# motor7.net
KiCad netlist of a schematic drawn in EAGLE
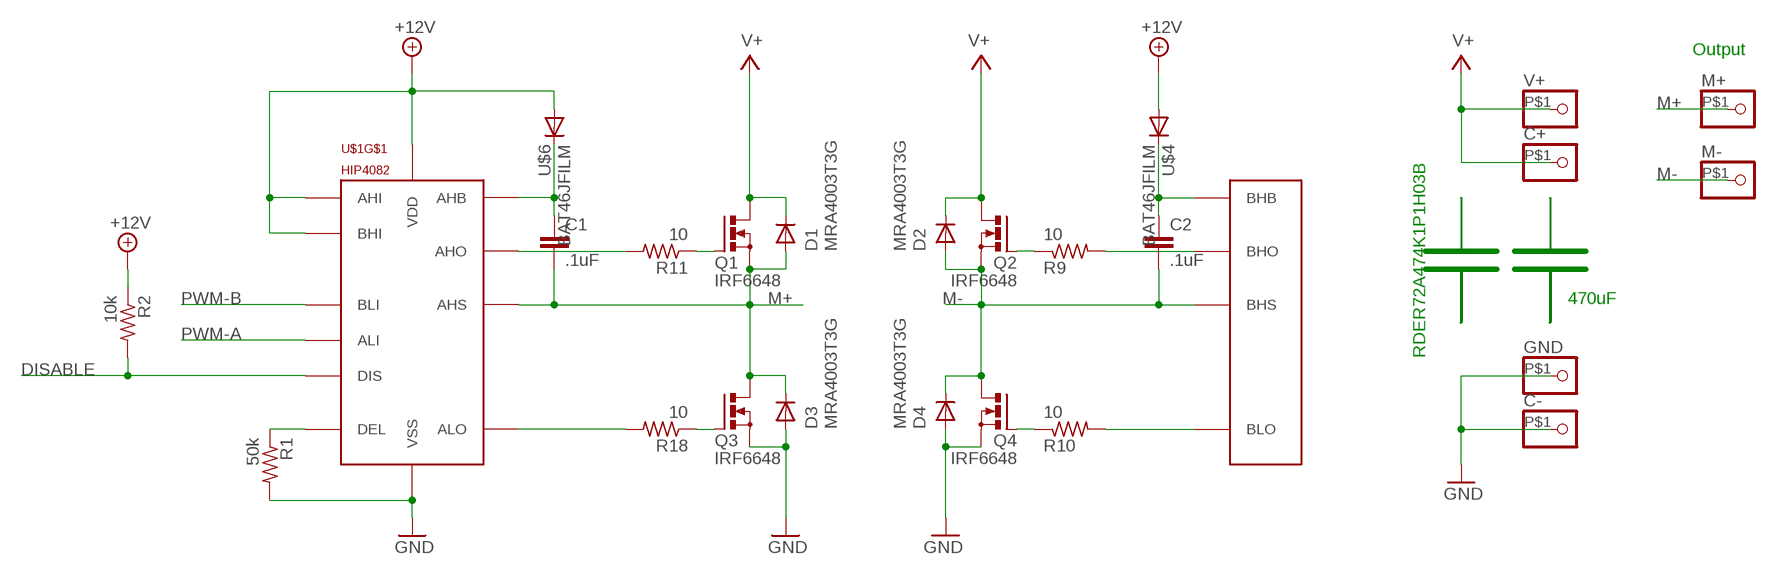
[diagram p0: schematic, sheet 1]
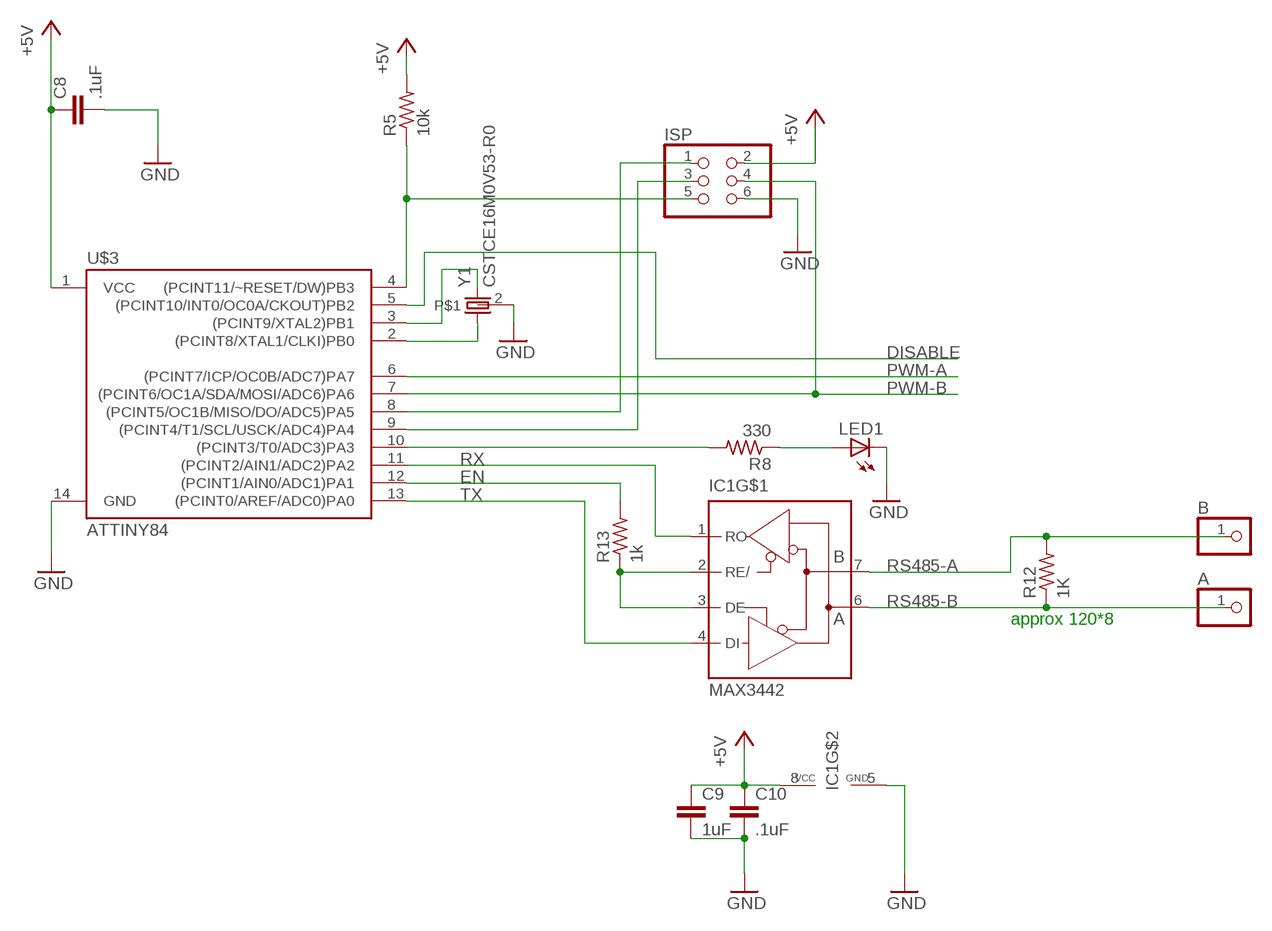
[diagram p1: schematic, sheet 2]
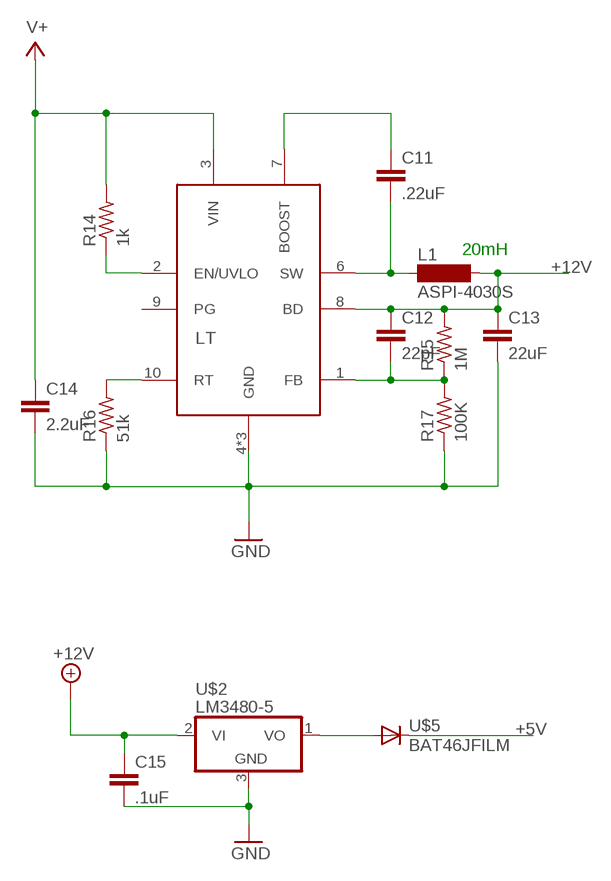
[diagram p2: schematic, sheet 3]

(export (version "E")
  (design (tool "Eeschema 10.0.6"))
  (components
    (comp (ref "A")
      (value "PINHD-1X1")
      (footprint "eagle-import:1X01")
      (libsource (lib "eagle-import") (part "pinhead_PINHD-1X1"))
    )
    (comp (ref "B")
      (value "PINHD-1X1")
      (footprint "eagle-import:1X01")
      (libsource (lib "eagle-import") (part "pinhead_PINHD-1X1"))
    )
    (comp (ref "C8")
      (value ".1uF")
      (footprint "eagle-import:C0603")
      (libsource (lib "eagle-import") (part "C-EUC0603"))
    )
    (comp (ref "C9")
      (value "1uF")
      (footprint "eagle-import:C0603")
      (libsource (lib "eagle-import") (part "C-EUC0603"))
    )
    (comp (ref "C10")
      (value ".1uF")
      (footprint "eagle-import:C0603")
      (libsource (lib "eagle-import") (part "C-EUC0603"))
    )
    (comp (ref "IC1")
      (value "MAX3442")
      (footprint "eagle-import:SO08")
      (fields (field (name "MF") "MAXIM") (field (name "MPN") "MAX481CSA"))
      (libsource (lib "eagle-import") (part "MAX3442"))
    )
    (comp (ref "ISP")
      (value "PINHD-2X3")
      (footprint "eagle-import:2X03")
      (libsource (lib "eagle-import") (part "PINHD-2X3"))
    )
    (comp (ref "LED1")
      (value "LEDCHIPLED_0603")
      (footprint "eagle-import:CHIPLED_0603")
      (libsource (lib "eagle-import") (part "LEDCHIPLED_0603"))
    )
    (comp (ref "R5")
      (value "10k")
      (footprint "eagle-import:R0603")
      (libsource (lib "eagle-import") (part "R-US_R0603"))
    )
    (comp (ref "R8")
      (value "330")
      (footprint "eagle-import:R0603")
      (libsource (lib "eagle-import") (part "R-US_R0603"))
    )
    (comp (ref "R12")
      (value "1K")
      (footprint "eagle-import:R0603")
      (libsource (lib "eagle-import") (part "R-US_R0603"))
    )
    (comp (ref "R13")
      (value "1k")
      (footprint "eagle-import:R0603")
      (libsource (lib "eagle-import") (part "R-US_R0603"))
    )
    (comp (ref "U$3")
      (value "ATTINY84")
      (footprint "eagle-import:SO14")
      (libsource (lib "eagle-import") (part "ATTINY84"))
    )
    (comp (ref "Y1")
      (value "CSTCE16M0V53-R0")
      (footprint "eagle-import:MYSMD2_RESONATOR")
      (libsource (lib "eagle-import") (part "CSTCE16M0V53-R0"))
    )
    (comp (ref "C11")
      (value ".22uF")
      (footprint "eagle-import:C0603")
      (libsource (lib "eagle-import") (part "C-EUC0603"))
    )
    (comp (ref "C12")
      (value "22pF")
      (footprint "eagle-import:C0603")
      (libsource (lib "eagle-import") (part "C-EUC0603"))
    )
    (comp (ref "C13")
      (value "22uF")
      (footprint "eagle-import:C0805")
      (libsource (lib "eagle-import") (part "C-EUC0805"))
    )
    (comp (ref "C14")
      (value "2.2uF")
      (footprint "eagle-import:C0603")
      (libsource (lib "eagle-import") (part "C-EUC0603"))
    )
    (comp (ref "C15")
      (value ".1uF")
      (footprint "eagle-import:C0603")
      (libsource (lib "eagle-import") (part "C-EUC0603"))
    )
    (comp (ref "L1")
      (value "ASPI-4030S")
      (footprint "eagle-import:ASPI-4030S")
      (libsource (lib "eagle-import") (part "ASPI-4030S"))
    )
    (comp (ref "LT")
      (value "LT3990")
      (footprint "eagle-import:DFN10-3X3")
      (libsource (lib "eagle-import") (part "LT3990"))
    )
    (comp (ref "R14")
      (value "1k")
      (footprint "eagle-import:R0603")
      (libsource (lib "eagle-import") (part "R-US_R0603"))
    )
    (comp (ref "R15")
      (value "1M")
      (footprint "eagle-import:R0603")
      (libsource (lib "eagle-import") (part "R-US_R0603"))
    )
    (comp (ref "R16")
      (value "51k")
      (footprint "eagle-import:R0603")
      (libsource (lib "eagle-import") (part "R-US_R0603"))
    )
    (comp (ref "R17")
      (value "100K")
      (footprint "eagle-import:R0603")
      (libsource (lib "eagle-import") (part "R-US_R0603"))
    )
    (comp (ref "U$2")
      (value "LM3480-5")
      (footprint "eagle-import:SOT23")
      (libsource (lib "eagle-import") (part "LM3480-5"))
    )
    (comp (ref "U$5")
      (value "BAT46JFILM")
      (footprint "eagle-import:SOD323")
      (libsource (lib "eagle-import") (part "BAT46JFILM"))
    )
    (comp (ref "C+")
      (value "PINHD-1X1")
      (footprint "eagle-import:1X01")
      (libsource (lib "eagle-import") (part "PINHD-1X1"))
    )
    (comp (ref "C-")
      (value "PINHD-1X1")
      (footprint "eagle-import:1X01")
      (libsource (lib "eagle-import") (part "PINHD-1X1"))
    )
    (comp (ref "C1")
      (value ".1uF")
      (footprint "eagle-import:C0603")
      (libsource (lib "eagle-import") (part "C-EUC0603"))
    )
    (comp (ref "C2")
      (value ".1uF")
      (footprint "eagle-import:C0603")
      (libsource (lib "eagle-import") (part "C-EUC0603"))
    )
    (comp (ref "D1")
      (value "MRA4003T3G")
      (footprint "eagle-import:SMA")
      (libsource (lib "eagle-import") (part "MRA4003T3G"))
    )
    (comp (ref "D2")
      (value "MRA4003T3G")
      (footprint "eagle-import:SMA")
      (libsource (lib "eagle-import") (part "MRA4003T3G"))
    )
    (comp (ref "D3")
      (value "MRA4003T3G")
      (footprint "eagle-import:SMA")
      (libsource (lib "eagle-import") (part "MRA4003T3G"))
    )
    (comp (ref "D4")
      (value "MRA4003T3G")
      (footprint "eagle-import:SMA")
      (libsource (lib "eagle-import") (part "MRA4003T3G"))
    )
    (comp (ref "GND")
      (value "PINHD-1X1")
      (footprint "eagle-import:1X01")
      (libsource (lib "eagle-import") (part "PINHD-1X1"))
    )
    (comp (ref "M+")
      (value "PINHD-1X1")
      (footprint "eagle-import:1X01")
      (libsource (lib "eagle-import") (part "PINHD-1X1"))
    )
    (comp (ref "M-")
      (value "PINHD-1X1")
      (footprint "eagle-import:1X01")
      (libsource (lib "eagle-import") (part "PINHD-1X1"))
    )
    (comp (ref "Q1")
      (value "IRF6648")
      (footprint "eagle-import:DIRECTFET-MOD")
      (libsource (lib "eagle-import") (part "IRF6648"))
    )
    (comp (ref "Q2")
      (value "IRF6648")
      (footprint "eagle-import:DIRECTFET-MOD")
      (libsource (lib "eagle-import") (part "IRF6648"))
    )
    (comp (ref "Q3")
      (value "IRF6648")
      (footprint "eagle-import:DIRECTFET")
      (libsource (lib "eagle-import") (part "transistor-power_IRF6648"))
    )
    (comp (ref "Q4")
      (value "IRF6648")
      (footprint "eagle-import:DIRECTFET")
      (libsource (lib "eagle-import") (part "transistor-power_IRF6648"))
    )
    (comp (ref "R1")
      (value "50k")
      (footprint "eagle-import:R0603")
      (libsource (lib "eagle-import") (part "R-US_R0603"))
    )
    (comp (ref "R2")
      (value "10k")
      (footprint "eagle-import:R0603")
      (libsource (lib "eagle-import") (part "R-US_R0603"))
    )
    (comp (ref "R9")
      (value "10")
      (footprint "eagle-import:R0603")
      (libsource (lib "eagle-import") (part "R-US_R0603"))
    )
    (comp (ref "R10")
      (value "10")
      (footprint "eagle-import:R0603")
      (libsource (lib "eagle-import") (part "R-US_R0603"))
    )
    (comp (ref "R11")
      (value "10")
      (footprint "eagle-import:R0603")
      (libsource (lib "eagle-import") (part "R-US_R0603"))
    )
    (comp (ref "R18")
      (value "10")
      (footprint "eagle-import:R0603")
      (libsource (lib "eagle-import") (part "R-US_R0603"))
    )
    (comp (ref "U$1")
      (value "HIP4082")
      (footprint "eagle-import:SOIC16")
      (libsource (lib "eagle-import") (part "HIP4082"))
    )
    (comp (ref "U$4")
      (value "BAT46JFILM")
      (footprint "eagle-import:SOD323")
      (libsource (lib "eagle-import") (part "BAT46JFILM"))
    )
    (comp (ref "U$6")
      (value "BAT46JFILM")
      (footprint "eagle-import:SOD323")
      (libsource (lib "eagle-import") (part "BAT46JFILM"))
    )
    (comp (ref "V+")
      (value "PINHD-1X1")
      (footprint "eagle-import:1X01")
      (libsource (lib "eagle-import") (part "PINHD-1X1"))
    )
  )
  (nets
    (net (code "1") (name "+5V") (class "Default")
      (node (ref "C10") (pin "1") (pinfunction "1_1") (pintype "passive"))
      (node (ref "C8") (pin "1") (pinfunction "1_1") (pintype "passive"))
      (node (ref "C9") (pin "1") (pinfunction "1_1") (pintype "passive"))
      (node (ref "IC1") (pin "8") (pinfunction "VCC_8") (pintype "power_in"))
      (node (ref "ISP") (pin "2") (pinfunction "2_2") (pintype "passive"))
      (node (ref "R5") (pin "2") (pinfunction "2_2") (pintype "passive"))
      (node (ref "U$3") (pin "1") (pinfunction "VCC_1") (pintype "bidirectional"))
      (node (ref "U$5") (pin "1") (pinfunction "C_1") (pintype "passive"))
    )
    (net (code "2") (name "+12V") (class "Default")
      (node (ref "C12") (pin "1") (pinfunction "1_1") (pintype "passive"))
      (node (ref "C13") (pin "1") (pinfunction "1_1") (pintype "passive"))
      (node (ref "C15") (pin "1") (pinfunction "1_1") (pintype "passive"))
      (node (ref "L1") (pin "P$2") (pinfunction "2_P$2") (pintype "passive"))
      (node (ref "LT") (pin "8") (pinfunction "BD_8") (pintype "bidirectional"))
      (node (ref "R15") (pin "2") (pinfunction "2_2") (pintype "passive"))
      (node (ref "R2") (pin "1") (pinfunction "1_1") (pintype "passive"))
      (node (ref "U$1") (pin "12") (pinfunction "VDD_12") (pintype "bidirectional"))
      (node (ref "U$1") (pin "2") (pinfunction "BHI_2") (pintype "bidirectional"))
      (node (ref "U$1") (pin "7") (pinfunction "AHI_7") (pintype "bidirectional"))
      (node (ref "U$2") (pin "2") (pinfunction "VI_2") (pintype "input"))
      (node (ref "U$4") (pin "2") (pinfunction "A_2") (pintype "passive"))
      (node (ref "U$6") (pin "2") (pinfunction "A_2") (pintype "passive"))
    )
    (net (code "3") (name "DISABLE") (class "Default")
      (node (ref "R2") (pin "2") (pinfunction "2_2") (pintype "passive"))
      (node (ref "U$1") (pin "8") (pinfunction "DIS_8") (pintype "bidirectional"))
      (node (ref "U$3") (pin "5") (pinfunction "(PCINT10/INT0/OC0A/CKOUT)PB2_5") (pintype "bidirectional"))
    )
    (net (code "4") (name "EN") (class "Default")
      (node (ref "R13") (pin "2") (pinfunction "2_2") (pintype "passive"))
      (node (ref "U$3") (pin "12") (pinfunction "(PCINT1/AIN0/ADC1)PA1_12") (pintype "bidirectional"))
    )
    (net (code "5") (name "GND") (class "Default")
      (node (ref "C-") (pin "P$1") (pinfunction "1_P$1") (pintype "passive"))
      (node (ref "C10") (pin "2") (pinfunction "2_2") (pintype "passive"))
      (node (ref "C13") (pin "2") (pinfunction "2_2") (pintype "passive"))
      (node (ref "C14") (pin "2") (pinfunction "2_2") (pintype "passive"))
      (node (ref "C15") (pin "2") (pinfunction "2_2") (pintype "passive"))
      (node (ref "C8") (pin "2") (pinfunction "2_2") (pintype "passive"))
      (node (ref "C9") (pin "2") (pinfunction "2_2") (pintype "passive"))
      (node (ref "D3") (pin "A") (pinfunction "A_A") (pintype "passive"))
      (node (ref "D4") (pin "A") (pinfunction "A_A") (pintype "passive"))
      (node (ref "GND") (pin "P$1") (pinfunction "1_P$1") (pintype "passive"))
      (node (ref "IC1") (pin "5") (pinfunction "GND_5") (pintype "power_in"))
      (node (ref "ISP") (pin "6") (pinfunction "6_6") (pintype "passive"))
      (node (ref "LED1") (pin "C") (pinfunction "C_C") (pintype "passive"))
      (node (ref "LT") (pin "4") (pinfunction "GND_4") (pintype "bidirectional"))
      (node (ref "LT") (pin "5") (pinfunction "GND_5") (pintype "bidirectional"))
      (node (ref "LT") (pin "EXP") (pinfunction "GND_EXP") (pintype "bidirectional"))
      (node (ref "Q3") (pin "S@1") (pinfunction "S_S@1") (pintype "passive"))
      (node (ref "Q3") (pin "S@2") (pinfunction "S_S@2") (pintype "passive"))
      (node (ref "Q4") (pin "S@1") (pinfunction "S_S@1") (pintype "passive"))
      (node (ref "Q4") (pin "S@2") (pinfunction "S_S@2") (pintype "passive"))
      (node (ref "R1") (pin "2") (pinfunction "2_2") (pintype "passive"))
      (node (ref "R16") (pin "1") (pinfunction "1_1") (pintype "passive"))
      (node (ref "R17") (pin "1") (pinfunction "1_1") (pintype "passive"))
      (node (ref "U$1") (pin "6") (pinfunction "VSS_6") (pintype "bidirectional"))
      (node (ref "U$2") (pin "3") (pinfunction "GND_3") (pintype "input"))
      (node (ref "U$3") (pin "14") (pinfunction "GND_14") (pintype "bidirectional"))
      (node (ref "Y1") (pin "2") (pinfunction "P$1_2") (pintype "bidirectional"))
    )
    (net (code "6") (name "M+") (class "Default")
      (node (ref "C1") (pin "2") (pinfunction "2_2") (pintype "passive"))
      (node (ref "D1") (pin "A") (pinfunction "A_A") (pintype "passive"))
      (node (ref "D3") (pin "C") (pinfunction "C_C") (pintype "passive"))
      (node (ref "M+") (pin "P$1") (pinfunction "1_P$1") (pintype "passive"))
      (node (ref "Q1") (pin "S@1") (pinfunction "S_S@1") (pintype "passive"))
      (node (ref "Q1") (pin "S@2") (pinfunction "S_S@2") (pintype "passive"))
      (node (ref "Q3") (pin "D@1") (pinfunction "D_D@1") (pintype "passive"))
      (node (ref "Q3") (pin "D@2") (pinfunction "D_D@2") (pintype "passive"))
      (node (ref "Q3") (pin "D@3") (pinfunction "D_D@3") (pintype "passive"))
      (node (ref "Q3") (pin "D@4") (pinfunction "D_D@4") (pintype "passive"))
      (node (ref "U$1") (pin "11") (pinfunction "AHS_11") (pintype "bidirectional"))
    )
    (net (code "7") (name "M-") (class "Default")
      (node (ref "C2") (pin "2") (pinfunction "2_2") (pintype "passive"))
      (node (ref "D2") (pin "A") (pinfunction "A_A") (pintype "passive"))
      (node (ref "D4") (pin "C") (pinfunction "C_C") (pintype "passive"))
      (node (ref "M-") (pin "P$1") (pinfunction "1_P$1") (pintype "passive"))
      (node (ref "Q2") (pin "S@1") (pinfunction "S_S@1") (pintype "passive"))
      (node (ref "Q2") (pin "S@2") (pinfunction "S_S@2") (pintype "passive"))
      (node (ref "Q4") (pin "D@1") (pinfunction "D_D@1") (pintype "passive"))
      (node (ref "Q4") (pin "D@2") (pinfunction "D_D@2") (pintype "passive"))
      (node (ref "Q4") (pin "D@3") (pinfunction "D_D@3") (pintype "passive"))
      (node (ref "Q4") (pin "D@4") (pinfunction "D_D@4") (pintype "passive"))
      (node (ref "U$1") (pin "15") (pinfunction "BHS_15") (pintype "bidirectional"))
    )
    (net (code "8") (name "Net-(IC1A-DE)") (class "Default")
      (node (ref "IC1") (pin "2") (pinfunction "RE/_2") (pintype "input"))
      (node (ref "IC1") (pin "3") (pinfunction "DE_3") (pintype "input"))
      (node (ref "R13") (pin "1") (pinfunction "1_1") (pintype "passive"))
    )
    (net (code "9") (name "Net-(L1-1)") (class "Default")
      (node (ref "C11") (pin "2") (pinfunction "2_2") (pintype "passive"))
      (node (ref "L1") (pin "P$1") (pinfunction "1_P$1") (pintype "passive"))
      (node (ref "LT") (pin "6") (pinfunction "SW_6") (pintype "bidirectional"))
    )
    (net (code "10") (name "Net-(LED1-PadA)") (class "Default")
      (node (ref "LED1") (pin "A") (pinfunction "A_A") (pintype "passive"))
      (node (ref "R8") (pin "1") (pinfunction "1_1") (pintype "passive"))
    )
    (net (code "11") (name "Net-(LT-BOOST)") (class "Default")
      (node (ref "C11") (pin "1") (pinfunction "1_1") (pintype "passive"))
      (node (ref "LT") (pin "7") (pinfunction "BOOST_7") (pintype "bidirectional"))
    )
    (net (code "12") (name "Net-(LT-EN{slash}UVLO)") (class "Default")
      (node (ref "LT") (pin "2") (pinfunction "EN/UVLO_2") (pintype "bidirectional"))
      (node (ref "R14") (pin "1") (pinfunction "1_1") (pintype "passive"))
    )
    (net (code "13") (name "Net-(LT-FB)") (class "Default")
      (node (ref "C12") (pin "2") (pinfunction "2_2") (pintype "passive"))
      (node (ref "LT") (pin "1") (pinfunction "FB_1") (pintype "bidirectional"))
      (node (ref "R15") (pin "1") (pinfunction "1_1") (pintype "passive"))
      (node (ref "R17") (pin "2") (pinfunction "2_2") (pintype "passive"))
    )
    (net (code "14") (name "Net-(LT-RT)") (class "Default")
      (node (ref "LT") (pin "10") (pinfunction "RT_10") (pintype "bidirectional"))
      (node (ref "R16") (pin "2") (pinfunction "2_2") (pintype "passive"))
    )
    (net (code "15") (name "Net-(Q1-PadG)") (class "Default")
      (node (ref "Q1") (pin "G") (pinfunction "G_G") (pintype "passive"))
      (node (ref "R11") (pin "1") (pinfunction "1_1") (pintype "passive"))
    )
    (net (code "16") (name "Net-(Q2-PadG)") (class "Default")
      (node (ref "Q2") (pin "G") (pinfunction "G_G") (pintype "passive"))
      (node (ref "R9") (pin "1") (pinfunction "1_1") (pintype "passive"))
    )
    (net (code "17") (name "Net-(Q3-PadG)") (class "Default")
      (node (ref "Q3") (pin "G") (pinfunction "G_G") (pintype "passive"))
      (node (ref "R18") (pin "1") (pinfunction "1_1") (pintype "passive"))
    )
    (net (code "18") (name "Net-(Q4-PadG)") (class "Default")
      (node (ref "Q4") (pin "G") (pinfunction "G_G") (pintype "passive"))
      (node (ref "R10") (pin "1") (pinfunction "1_1") (pintype "passive"))
    )
    (net (code "19") (name "Net-(U$1A-AHB)") (class "Default")
      (node (ref "C1") (pin "1") (pinfunction "1_1") (pintype "passive"))
      (node (ref "U$1") (pin "9") (pinfunction "AHB_9") (pintype "bidirectional"))
      (node (ref "U$6") (pin "1") (pinfunction "C_1") (pintype "passive"))
    )
    (net (code "20") (name "Net-(U$1A-AHO)") (class "Default")
      (node (ref "R11") (pin "2") (pinfunction "2_2") (pintype "passive"))
      (node (ref "U$1") (pin "10") (pinfunction "AHO_10") (pintype "bidirectional"))
    )
    (net (code "21") (name "Net-(U$1A-ALO)") (class "Default")
      (node (ref "R18") (pin "2") (pinfunction "2_2") (pintype "passive"))
      (node (ref "U$1") (pin "13") (pinfunction "ALO_13") (pintype "bidirectional"))
    )
    (net (code "22") (name "Net-(U$1A-DEL)") (class "Default")
      (node (ref "R1") (pin "1") (pinfunction "1_1") (pintype "passive"))
      (node (ref "U$1") (pin "5") (pinfunction "DEL_5") (pintype "bidirectional"))
    )
    (net (code "23") (name "Net-(U$1B-BHB)") (class "Default")
      (node (ref "C2") (pin "1") (pinfunction "1_1") (pintype "passive"))
      (node (ref "U$1") (pin "1") (pinfunction "BHB_1") (pintype "bidirectional"))
      (node (ref "U$4") (pin "1") (pinfunction "C_1") (pintype "passive"))
    )
    (net (code "24") (name "Net-(U$1B-BHO)") (class "Default")
      (node (ref "R9") (pin "2") (pinfunction "2_2") (pintype "passive"))
      (node (ref "U$1") (pin "16") (pinfunction "BHO_16") (pintype "bidirectional"))
    )
    (net (code "25") (name "Net-(U$1B-BLO)") (class "Default")
      (node (ref "R10") (pin "2") (pinfunction "2_2") (pintype "passive"))
      (node (ref "U$1") (pin "14") (pinfunction "BLO_14") (pintype "bidirectional"))
    )
    (net (code "26") (name "Net-(U$2-VO)") (class "Default")
      (node (ref "U$2") (pin "1") (pinfunction "VO_1") (pintype "passive"))
      (node (ref "U$5") (pin "2") (pinfunction "A_2") (pintype "passive"))
    )
    (net (code "27") (name "Net-(U$3-(PCINT3{slash}T0{slash}ADC3)PA3)") (class "Default")
      (node (ref "R8") (pin "2") (pinfunction "2_2") (pintype "passive"))
      (node (ref "U$3") (pin "10") (pinfunction "(PCINT3/T0/ADC3)PA3_10") (pintype "bidirectional"))
    )
    (net (code "28") (name "Net-(U$3-(PCINT4{slash}T1{slash}SCL{slash}USCK{slash}ADC4)PA4)") (class "Default")
      (node (ref "ISP") (pin "3") (pinfunction "3_3") (pintype "passive"))
      (node (ref "U$3") (pin "9") (pinfunction "(PCINT4/T1/SCL/USCK/ADC4)PA4_9") (pintype "bidirectional"))
    )
    (net (code "29") (name "Net-(U$3-(PCINT5{slash}OC1B{slash}MISO{slash}DO{slash}ADC5)PA5)") (class "Default")
      (node (ref "ISP") (pin "1") (pinfunction "1_1") (pintype "passive"))
      (node (ref "U$3") (pin "8") (pinfunction "(PCINT5/OC1B/MISO/DO/ADC5)PA5_8") (pintype "bidirectional"))
    )
    (net (code "30") (name "Net-(U$3-(PCINT8{slash}XTAL1{slash}CLKI)PB0)") (class "Default")
      (node (ref "U$3") (pin "2") (pinfunction "(PCINT8/XTAL1/CLKI)PB0_2") (pintype "bidirectional"))
      (node (ref "Y1") (pin "1") (pinfunction "1_1") (pintype "passive"))
    )
    (net (code "31") (name "Net-(U$3-(PCINT9{slash}XTAL2)PB1)") (class "Default")
      (node (ref "U$3") (pin "3") (pinfunction "(PCINT9/XTAL2)PB1_3") (pintype "bidirectional"))
      (node (ref "Y1") (pin "3") (pinfunction "2_3") (pintype "passive"))
    )
    (net (code "32") (name "Net-(U$3-(PCINT11{slash}~{RESET{slash}DW})PB3)") (class "Default")
      (node (ref "ISP") (pin "5") (pinfunction "5_5") (pintype "passive"))
      (node (ref "R5") (pin "1") (pinfunction "1_1") (pintype "passive"))
      (node (ref "U$3") (pin "4") (pinfunction "(PCINT11/~{RESET/DW})PB3_4") (pintype "bidirectional"))
    )
    (net (code "33") (name "PWM-A") (class "Default")
      (node (ref "U$1") (pin "4") (pinfunction "ALI_4") (pintype "bidirectional"))
      (node (ref "U$3") (pin "6") (pinfunction "(PCINT7/ICP/OC0B/ADC7)PA7_6") (pintype "bidirectional"))
    )
    (net (code "34") (name "PWM-B") (class "Default")
      (node (ref "ISP") (pin "4") (pinfunction "4_4") (pintype "passive"))
      (node (ref "U$1") (pin "3") (pinfunction "BLI_3") (pintype "bidirectional"))
      (node (ref "U$3") (pin "7") (pinfunction "(PCINT6/OC1A/SDA/MOSI/ADC6)PA6_7") (pintype "bidirectional"))
    )
    (net (code "35") (name "RS485-A") (class "Default")
      (node (ref "B") (pin "1") (pinfunction "1_1") (pintype "passive"))
      (node (ref "IC1") (pin "7") (pinfunction "B_7") (pintype "passive"))
      (node (ref "R12") (pin "2") (pinfunction "2_2") (pintype "passive"))
    )
    (net (code "36") (name "RS485-B") (class "Default")
      (node (ref "A") (pin "1") (pinfunction "1_1") (pintype "passive"))
      (node (ref "IC1") (pin "6") (pinfunction "A_6") (pintype "passive"))
      (node (ref "R12") (pin "1") (pinfunction "1_1") (pintype "passive"))
    )
    (net (code "37") (name "RX") (class "Default")
      (node (ref "IC1") (pin "1") (pinfunction "RO_1") (pintype "output"))
      (node (ref "U$3") (pin "11") (pinfunction "(PCINT2/AIN1/ADC2)PA2_11") (pintype "bidirectional"))
    )
    (net (code "38") (name "TX") (class "Default")
      (node (ref "IC1") (pin "4") (pinfunction "DI_4") (pintype "input"))
      (node (ref "U$3") (pin "13") (pinfunction "(PCINT0/AREF/ADC0)PA0_13") (pintype "bidirectional"))
    )
    (net (code "39") (name "V+") (class "Default")
      (node (ref "C+") (pin "P$1") (pinfunction "1_P$1") (pintype "passive"))
      (node (ref "C14") (pin "1") (pinfunction "1_1") (pintype "passive"))
      (node (ref "D1") (pin "C") (pinfunction "C_C") (pintype "passive"))
      (node (ref "D2") (pin "C") (pinfunction "C_C") (pintype "passive"))
      (node (ref "LT") (pin "3") (pinfunction "VIN_3") (pintype "bidirectional"))
      (node (ref "Q1") (pin "D@1") (pinfunction "D_D@1") (pintype "passive"))
      (node (ref "Q1") (pin "D@2") (pinfunction "D_D@2") (pintype "passive"))
      (node (ref "Q1") (pin "D@3") (pinfunction "D_D@3") (pintype "passive"))
      (node (ref "Q1") (pin "D@4") (pinfunction "D_D@4") (pintype "passive"))
      (node (ref "Q2") (pin "D@1") (pinfunction "D_D@1") (pintype "passive"))
      (node (ref "Q2") (pin "D@2") (pinfunction "D_D@2") (pintype "passive"))
      (node (ref "Q2") (pin "D@3") (pinfunction "D_D@3") (pintype "passive"))
      (node (ref "Q2") (pin "D@4") (pinfunction "D_D@4") (pintype "passive"))
      (node (ref "R14") (pin "2") (pinfunction "2_2") (pintype "passive"))
      (node (ref "V+") (pin "P$1") (pinfunction "1_P$1") (pintype "passive"))
    )
    (net (code "40") (name "unconnected-(LT-PG-Pad9)") (class "Default")
      (node (ref "LT") (pin "9") (pinfunction "PG_9") (pintype "bidirectional"))
    )
  )
)
